# AR20_ETBC_rev1.net
KiCad netlist of a schematic drawn in EAGLE
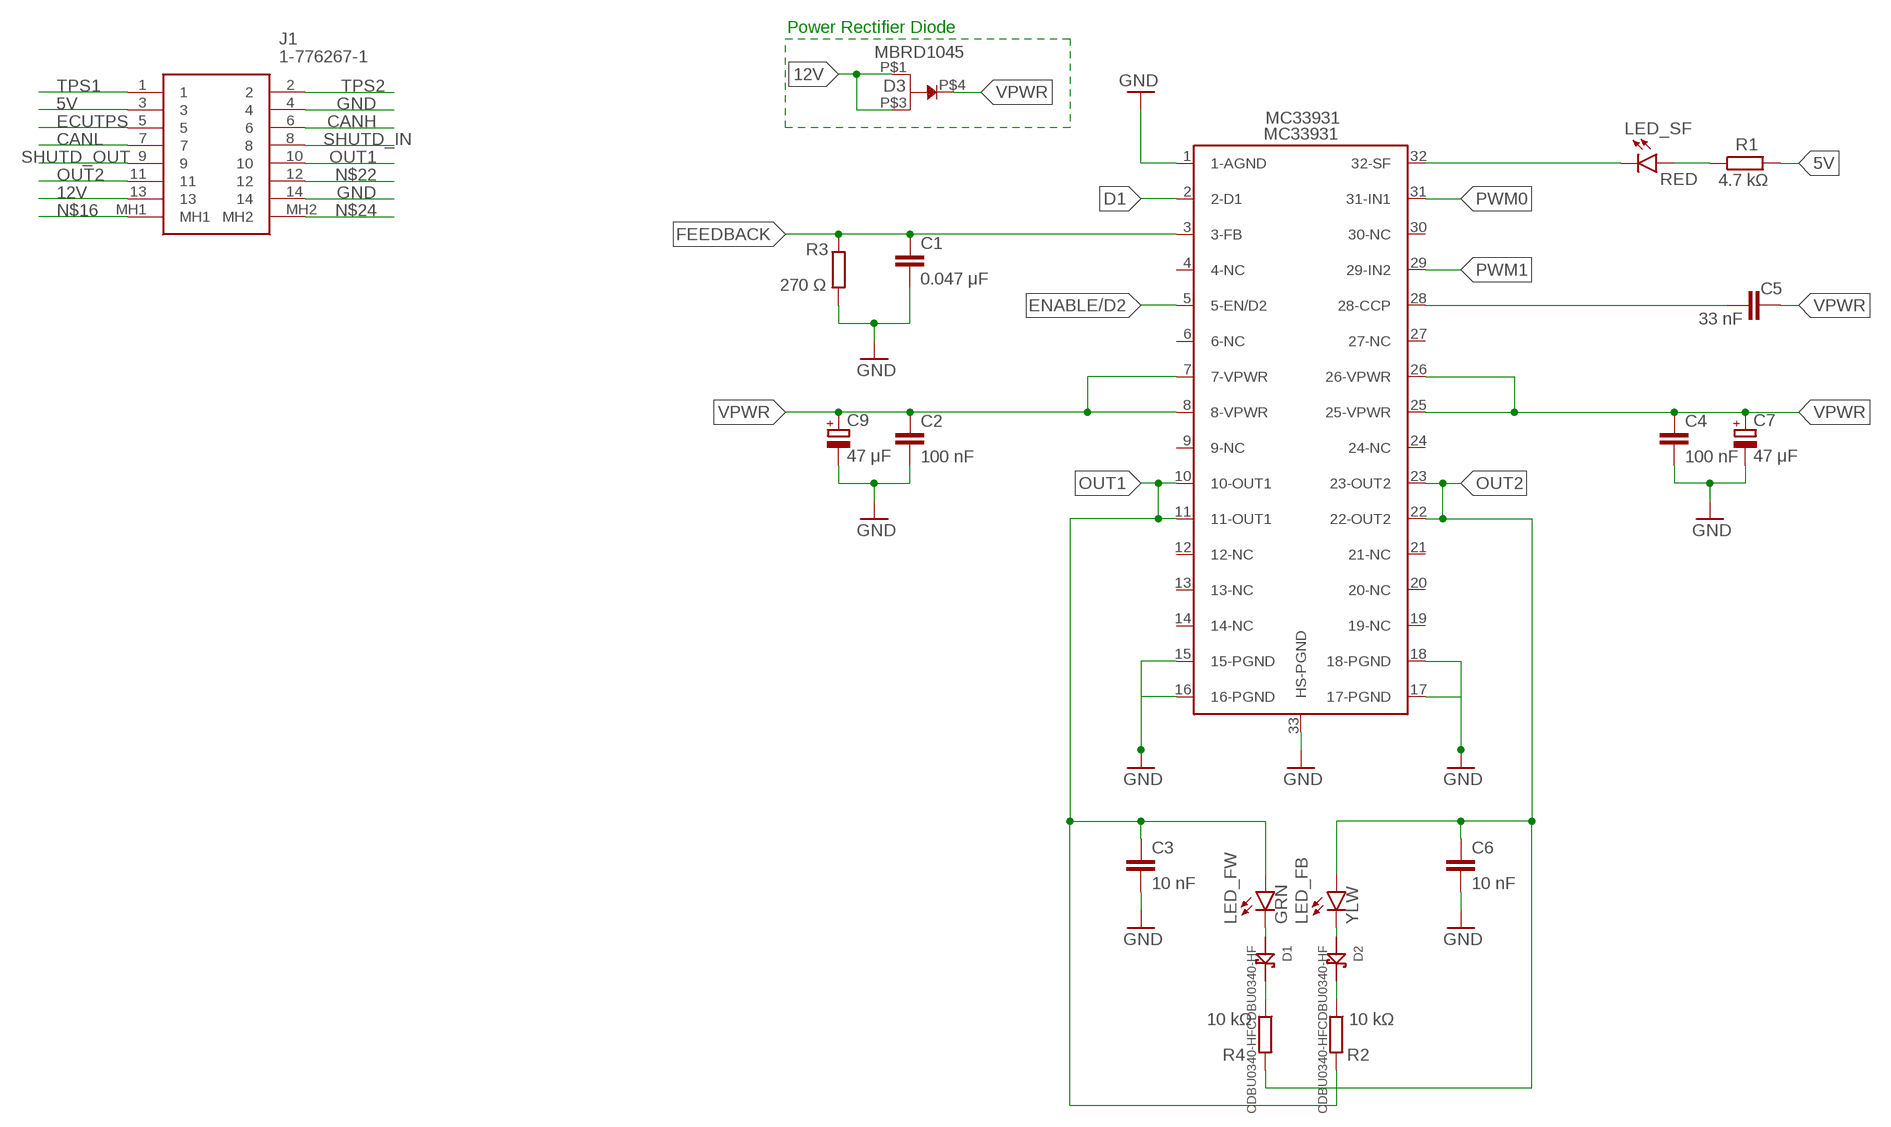
[diagram p0: schematic, sheet 1]

(export (version "E")
  (design (tool "Eeschema 10.0.6"))
  (components
    (comp (ref "C1")
      (value "0.047 μF")
      (footprint "eagle-import:C0603")
      (libsource (lib "eagle-import") (part "C-EUC0603"))
    )
    (comp (ref "C2")
      (value "100 nF")
      (footprint "eagle-import:C0603")
      (libsource (lib "eagle-import") (part "C-EUC0603"))
    )
    (comp (ref "C3")
      (value "10 nF")
      (footprint "eagle-import:C0603")
      (libsource (lib "eagle-import") (part "C-EUC0603"))
    )
    (comp (ref "C4")
      (value "100 nF")
      (footprint "eagle-import:C0603")
      (libsource (lib "eagle-import") (part "C-EUC0603"))
    )
    (comp (ref "C5")
      (value "33 nF")
      (footprint "eagle-import:C0603")
      (libsource (lib "eagle-import") (part "C-EUC0603"))
    )
    (comp (ref "C6")
      (value "10 nF")
      (footprint "eagle-import:C0603")
      (libsource (lib "eagle-import") (part "C-EUC0603"))
    )
    (comp (ref "C7")
      (value "47 μF")
      (footprint "eagle-import:B45181A")
      (libsource (lib "eagle-import") (part "CPOL-EUB45181A"))
    )
    (comp (ref "C9")
      (value "47 μF")
      (footprint "eagle-import:B45181A")
      (libsource (lib "eagle-import") (part "CPOL-EUB45181A"))
    )
    (comp (ref "D1")
      (value "CDBU0340-HFCDBU0340-HF")
      (footprint "eagle-import:DIOM1709X85")
      (libsource (lib "eagle-import") (part "CDBU0340-HFCDBU0340-HF"))
    )
    (comp (ref "D2")
      (value "CDBU0340-HFCDBU0340-HF")
      (footprint "eagle-import:DIOM1709X85")
      (libsource (lib "eagle-import") (part "CDBU0340-HFCDBU0340-HF"))
    )
    (comp (ref "D3")
      (value "MBRD1045")
      (footprint "eagle-import:DPAK")
      (libsource (lib "eagle-import") (part "MBRD1045"))
    )
    (comp (ref "J1")
      (value "1-776267-1")
      (footprint "eagle-import:17762671")
      (fields (field (name "MOUSER_PART_NUMBER") "571-1-776267-1"))
      (libsource (lib "eagle-import") (part "1-776267-1"))
    )
    (comp (ref "LED_FB")
      (value "YLW")
      (footprint "eagle-import:SML1206")
      (libsource (lib "eagle-import") (part "LEDSML1206"))
    )
    (comp (ref "LED_FW")
      (value "GRN")
      (footprint "eagle-import:SML1206")
      (libsource (lib "eagle-import") (part "LEDSML1206"))
    )
    (comp (ref "LED_SF")
      (value "RED")
      (footprint "eagle-import:SML1206")
      (libsource (lib "eagle-import") (part "LEDSML1206"))
    )
    (comp (ref "MC33931")
      (value "MC33931")
      (footprint "eagle-import:SOP65P1030X245-33T480X861")
      (libsource (lib "eagle-import") (part "MC33931"))
    )
    (comp (ref "R1")
      (value "4.7 kΩ")
      (footprint "eagle-import:R0603")
      (libsource (lib "eagle-import") (part "R-EU_R0603"))
    )
    (comp (ref "R2")
      (value "10 kΩ")
      (footprint "eagle-import:R0603")
      (libsource (lib "eagle-import") (part "R-EU_R0603"))
    )
    (comp (ref "R3")
      (value "270 Ω")
      (footprint "eagle-import:R0603")
      (libsource (lib "eagle-import") (part "R-EU_R0603"))
    )
    (comp (ref "R4")
      (value "10 kΩ")
      (footprint "eagle-import:R0603")
      (libsource (lib "eagle-import") (part "R-EU_R0603"))
    )
  )
  (nets
    (net (code "1") (name "/CANH") (class "Default")
      (node (ref "J1") (pin "6") (pinfunction "6_6") (pintype "bidirectional"))
    )
    (net (code "2") (name "/CANL") (class "Default")
      (node (ref "J1") (pin "7") (pinfunction "7_7") (pintype "bidirectional"))
    )
    (net (code "3") (name "/ECUTPS") (class "Default")
      (node (ref "J1") (pin "5") (pinfunction "5_5") (pintype "bidirectional"))
    )
    (net (code "4") (name "/N$16") (class "Default")
      (node (ref "J1") (pin "MH1") (pinfunction "MH1_MH1") (pintype "bidirectional"))
    )
    (net (code "5") (name "/N$22") (class "Default")
      (node (ref "J1") (pin "12") (pinfunction "12_12") (pintype "bidirectional"))
    )
    (net (code "6") (name "/N$24") (class "Default")
      (node (ref "J1") (pin "MH2") (pinfunction "MH2_MH2") (pintype "bidirectional"))
    )
    (net (code "7") (name "/SHUTD_IN") (class "Default")
      (node (ref "J1") (pin "8") (pinfunction "8_8") (pintype "bidirectional"))
    )
    (net (code "8") (name "/SHUTD_OUT") (class "Default")
      (node (ref "J1") (pin "9") (pinfunction "9_9") (pintype "bidirectional"))
    )
    (net (code "9") (name "/TPS1") (class "Default")
      (node (ref "J1") (pin "1") (pinfunction "1_1") (pintype "bidirectional"))
    )
    (net (code "10") (name "/TPS2") (class "Default")
      (node (ref "J1") (pin "2") (pinfunction "2_2") (pintype "bidirectional"))
    )
    (net (code "11") (name "5V") (class "Default")
      (node (ref "J1") (pin "3") (pinfunction "3_3") (pintype "bidirectional"))
      (node (ref "R1") (pin "2") (pinfunction "2_2") (pintype "passive"))
    )
    (net (code "12") (name "12V") (class "Default")
      (node (ref "D3") (pin "P$1") (pinfunction "P$1_P$1") (pintype "input"))
      (node (ref "D3") (pin "P$3") (pinfunction "P$3_P$3") (pintype "input"))
      (node (ref "J1") (pin "13") (pinfunction "13_13") (pintype "bidirectional"))
    )
    (net (code "13") (name "D1") (class "Default")
      (node (ref "MC33931") (pin "2") (pinfunction "2-D1_2") (pintype "bidirectional"))
    )
    (net (code "14") (name "ENABLE{slash}D2") (class "Default")
      (node (ref "MC33931") (pin "5") (pinfunction "5-EN/D2_5") (pintype "bidirectional"))
    )
    (net (code "15") (name "FEEDBACK") (class "Default")
      (node (ref "C1") (pin "1") (pinfunction "1_1") (pintype "passive"))
      (node (ref "MC33931") (pin "3") (pinfunction "3-FB_3") (pintype "bidirectional"))
      (node (ref "R3") (pin "2") (pinfunction "2_2") (pintype "passive"))
    )
    (net (code "16") (name "GND") (class "Default")
      (node (ref "C1") (pin "2") (pinfunction "2_2") (pintype "passive"))
      (node (ref "C2") (pin "2") (pinfunction "2_2") (pintype "passive"))
      (node (ref "C3") (pin "2") (pinfunction "2_2") (pintype "passive"))
      (node (ref "C4") (pin "2") (pinfunction "2_2") (pintype "passive"))
      (node (ref "C6") (pin "2") (pinfunction "2_2") (pintype "passive"))
      (node (ref "C7") (pin "-") (pinfunction "-_-") (pintype "passive"))
      (node (ref "C9") (pin "-") (pinfunction "-_-") (pintype "passive"))
      (node (ref "J1") (pin "14") (pinfunction "14_14") (pintype "bidirectional"))
      (node (ref "J1") (pin "4") (pinfunction "4_4") (pintype "bidirectional"))
      (node (ref "MC33931") (pin "1") (pinfunction "1-AGND_1") (pintype "bidirectional"))
      (node (ref "MC33931") (pin "15") (pinfunction "15-PGND_15") (pintype "bidirectional"))
      (node (ref "MC33931") (pin "16") (pinfunction "16-PGND_16") (pintype "bidirectional"))
      (node (ref "MC33931") (pin "17") (pinfunction "17-PGND_17") (pintype "bidirectional"))
      (node (ref "MC33931") (pin "18") (pinfunction "18-PGND_18") (pintype "bidirectional"))
      (node (ref "MC33931") (pin "33") (pinfunction "HS-PGND_33") (pintype "bidirectional"))
      (node (ref "R3") (pin "1") (pinfunction "1_1") (pintype "passive"))
    )
    (net (code "17") (name "Net-(D1-A)") (class "Default")
      (node (ref "D1") (pin "2$A") (pinfunction "A_2$A") (pintype "input"))
      (node (ref "LED_FW") (pin "C") (pinfunction "C_C") (pintype "passive"))
    )
    (net (code "18") (name "Net-(D1-K)") (class "Default")
      (node (ref "D1") (pin "1$K") (pinfunction "K_1$K") (pintype "input"))
      (node (ref "R4") (pin "1") (pinfunction "1_1") (pintype "passive"))
    )
    (net (code "19") (name "Net-(D2-A)") (class "Default")
      (node (ref "D2") (pin "2$A") (pinfunction "A_2$A") (pintype "input"))
      (node (ref "LED_FB") (pin "C") (pinfunction "C_C") (pintype "passive"))
    )
    (net (code "20") (name "Net-(D2-K)") (class "Default")
      (node (ref "D2") (pin "1$K") (pinfunction "K_1$K") (pintype "input"))
      (node (ref "R2") (pin "1") (pinfunction "1_1") (pintype "passive"))
    )
    (net (code "21") (name "Net-(LED_SF-PadA)") (class "Default")
      (node (ref "LED_SF") (pin "A") (pinfunction "A_A") (pintype "passive"))
      (node (ref "R1") (pin "1") (pinfunction "1_1") (pintype "passive"))
    )
    (net (code "22") (name "Net-(MC33931-28-CCP)") (class "Default")
      (node (ref "C5") (pin "1") (pinfunction "1_1") (pintype "passive"))
      (node (ref "MC33931") (pin "28") (pinfunction "28-CCP_28") (pintype "bidirectional"))
    )
    (net (code "23") (name "Net-(MC33931-32-SF)") (class "Default")
      (node (ref "LED_SF") (pin "C") (pinfunction "C_C") (pintype "passive"))
      (node (ref "MC33931") (pin "32") (pinfunction "32-SF_32") (pintype "bidirectional"))
    )
    (net (code "24") (name "OUT1") (class "Default")
      (node (ref "C3") (pin "1") (pinfunction "1_1") (pintype "passive"))
      (node (ref "J1") (pin "10") (pinfunction "10_10") (pintype "bidirectional"))
      (node (ref "LED_FW") (pin "A") (pinfunction "A_A") (pintype "passive"))
      (node (ref "MC33931") (pin "10") (pinfunction "10-OUT1_10") (pintype "bidirectional"))
      (node (ref "MC33931") (pin "11") (pinfunction "11-OUT1_11") (pintype "bidirectional"))
      (node (ref "R2") (pin "2") (pinfunction "2_2") (pintype "passive"))
    )
    (net (code "25") (name "OUT2") (class "Default")
      (node (ref "C6") (pin "1") (pinfunction "1_1") (pintype "passive"))
      (node (ref "J1") (pin "11") (pinfunction "11_11") (pintype "bidirectional"))
      (node (ref "LED_FB") (pin "A") (pinfunction "A_A") (pintype "passive"))
      (node (ref "MC33931") (pin "22") (pinfunction "22-OUT2_22") (pintype "bidirectional"))
      (node (ref "MC33931") (pin "23") (pinfunction "23-OUT2_23") (pintype "bidirectional"))
      (node (ref "R4") (pin "2") (pinfunction "2_2") (pintype "passive"))
    )
    (net (code "26") (name "PWM0") (class "Default")
      (node (ref "MC33931") (pin "31") (pinfunction "31-IN1_31") (pintype "bidirectional"))
    )
    (net (code "27") (name "PWM1") (class "Default")
      (node (ref "MC33931") (pin "29") (pinfunction "29-IN2_29") (pintype "bidirectional"))
    )
    (net (code "28") (name "VPWR") (class "Default")
      (node (ref "C2") (pin "1") (pinfunction "1_1") (pintype "passive"))
      (node (ref "C4") (pin "1") (pinfunction "1_1") (pintype "passive"))
      (node (ref "C5") (pin "2") (pinfunction "2_2") (pintype "passive"))
      (node (ref "C7") (pin "+") (pinfunction "+_+") (pintype "passive"))
      (node (ref "C9") (pin "+") (pinfunction "+_+") (pintype "passive"))
      (node (ref "D3") (pin "P$4") (pinfunction "P$4_P$4") (pintype "output"))
      (node (ref "MC33931") (pin "25") (pinfunction "25-VPWR_25") (pintype "bidirectional"))
      (node (ref "MC33931") (pin "26") (pinfunction "26-VPWR_26") (pintype "bidirectional"))
      (node (ref "MC33931") (pin "7") (pinfunction "7-VPWR_7") (pintype "bidirectional"))
      (node (ref "MC33931") (pin "8") (pinfunction "8-VPWR_8") (pintype "bidirectional"))
    )
    (net (code "29") (name "unconnected-(MC33931-4-NC-Pad4)") (class "Default")
      (node (ref "MC33931") (pin "4") (pinfunction "4-NC_4") (pintype "bidirectional"))
    )
    (net (code "30") (name "unconnected-(MC33931-6-NC-Pad6)") (class "Default")
      (node (ref "MC33931") (pin "6") (pinfunction "6-NC_6") (pintype "bidirectional"))
    )
    (net (code "31") (name "unconnected-(MC33931-9-NC-Pad9)") (class "Default")
      (node (ref "MC33931") (pin "9") (pinfunction "9-NC_9") (pintype "bidirectional"))
    )
    (net (code "32") (name "unconnected-(MC33931-12-NC-Pad12)") (class "Default")
      (node (ref "MC33931") (pin "12") (pinfunction "12-NC_12") (pintype "bidirectional"))
    )
    (net (code "33") (name "unconnected-(MC33931-13-NC-Pad13)") (class "Default")
      (node (ref "MC33931") (pin "13") (pinfunction "13-NC_13") (pintype "bidirectional"))
    )
    (net (code "34") (name "unconnected-(MC33931-14-NC-Pad14)") (class "Default")
      (node (ref "MC33931") (pin "14") (pinfunction "14-NC_14") (pintype "bidirectional"))
    )
    (net (code "35") (name "unconnected-(MC33931-19-NC-Pad19)") (class "Default")
      (node (ref "MC33931") (pin "19") (pinfunction "19-NC_19") (pintype "bidirectional"))
    )
    (net (code "36") (name "unconnected-(MC33931-20-NC-Pad20)") (class "Default")
      (node (ref "MC33931") (pin "20") (pinfunction "20-NC_20") (pintype "bidirectional"))
    )
    (net (code "37") (name "unconnected-(MC33931-21-NC-Pad21)") (class "Default")
      (node (ref "MC33931") (pin "21") (pinfunction "21-NC_21") (pintype "bidirectional"))
    )
    (net (code "38") (name "unconnected-(MC33931-24-NC-Pad24)") (class "Default")
      (node (ref "MC33931") (pin "24") (pinfunction "24-NC_24") (pintype "bidirectional"))
    )
    (net (code "39") (name "unconnected-(MC33931-27-NC-Pad27)") (class "Default")
      (node (ref "MC33931") (pin "27") (pinfunction "27-NC_27") (pintype "bidirectional"))
    )
    (net (code "40") (name "unconnected-(MC33931-30-NC-Pad30)") (class "Default")
      (node (ref "MC33931") (pin "30") (pinfunction "30-NC_30") (pintype "bidirectional"))
    )
  )
)
